# RelayBoard1.net
KiCad netlist of a schematic drawn in EAGLE
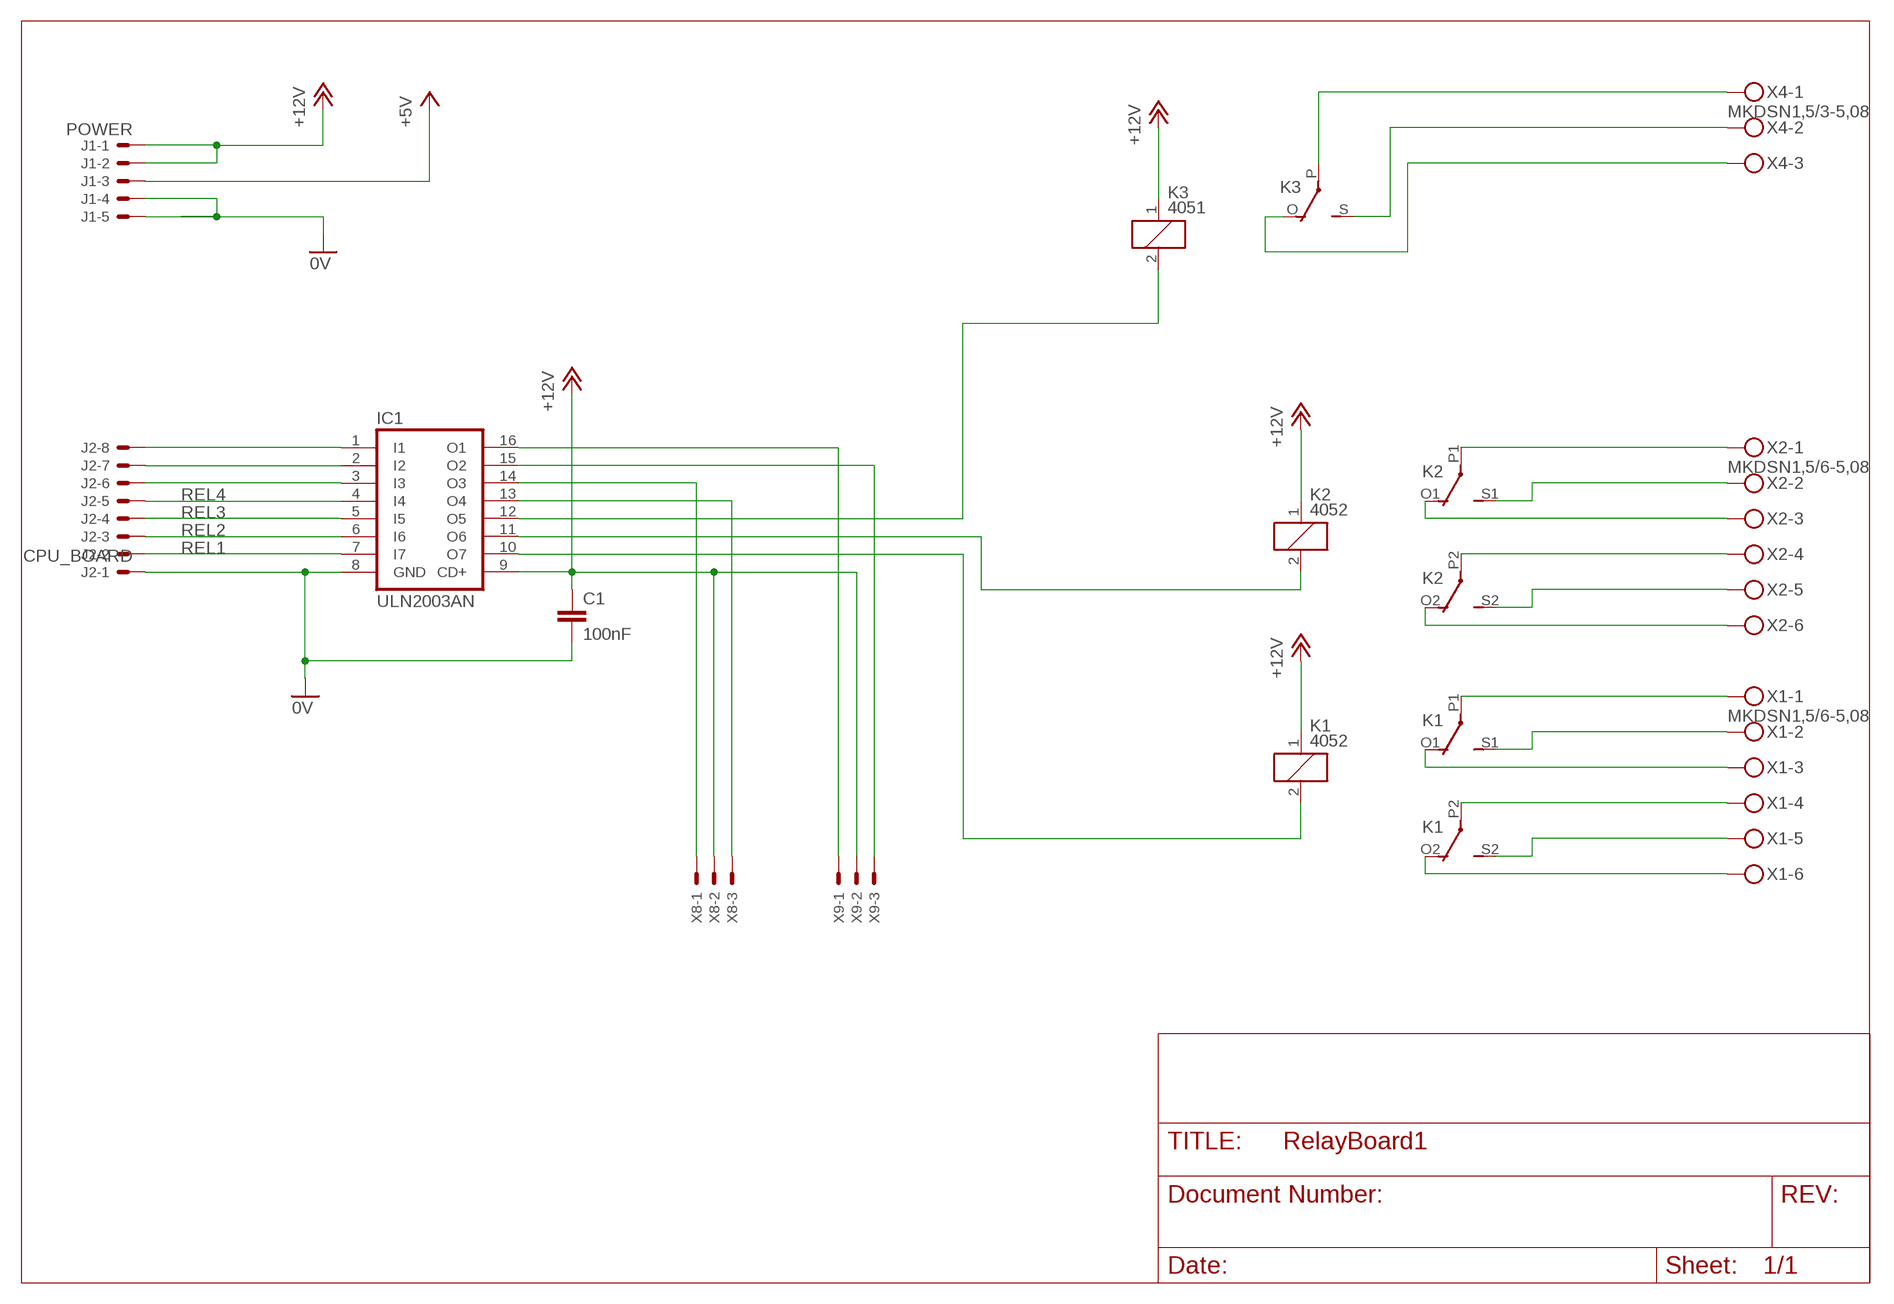
[diagram p0: schematic, sheet 1]

(export (version "E")
  (design (tool "Eeschema 10.0.6"))
  (components
    (comp (ref "C1")
      (value "100nF")
      (footprint "eagle-import:C025-025X050")
      (libsource (lib "eagle-import") (part "C-EU025-025X050"))
    )
    (comp (ref "IC1")
      (value "ULN2003AN")
      (footprint "eagle-import:DIL16")
      (libsource (lib "eagle-import") (part "ULN2003AN"))
    )
    (comp (ref "J1")
      (value "POWER")
      (footprint "eagle-import:6410-05")
      (libsource (lib "eagle-import") (part "22-?-0527-2051"))
    )
    (comp (ref "J2")
      (value "CPU_BOARD")
      (footprint "eagle-import:6410-08")
      (libsource (lib "eagle-import") (part "22-?-0827-2081"))
    )
    (comp (ref "K1")
      (value "4052")
      (footprint "eagle-import:F4052")
      (libsource (lib "eagle-import") (part "4052"))
    )
    (comp (ref "K2")
      (value "4052")
      (footprint "eagle-import:F4052")
      (libsource (lib "eagle-import") (part "4052"))
    )
    (comp (ref "K3")
      (value "4051")
      (footprint "eagle-import:G2R")
      (fields (field (name "OC_FARNELL") "1569185"))
      (libsource (lib "eagle-import") (part "G2R"))
    )
    (comp (ref "X1")
      (value "MKDSN1,5/6-5,08")
      (footprint "eagle-import:MKDSN1,5_6-5,08")
      (fields (field (name "MPN") "SMKDSN1,5/6-5,08"))
      (libsource (lib "eagle-import") (part "MKDSN1,5/6-5,08"))
    )
    (comp (ref "X2")
      (value "MKDSN1,5/6-5,08")
      (footprint "eagle-import:MKDSN1,5_6-5,08")
      (fields (field (name "MPN") "SMKDSN1,5/6-5,08"))
      (libsource (lib "eagle-import") (part "MKDSN1,5/6-5,08"))
    )
    (comp (ref "X4")
      (value "MKDSN1,5/3-5,08")
      (footprint "eagle-import:MKDSN1,5_3-5,08")
      (fields
        (field (name "MPN") "SMKDSN1,5/3-5,08")
        (field (name "MPN_1") "SMKDSN1,5/3-5,08")
        (field (name "OC_FARNELL") "1792904")
        (field (name "OC_NEWARK") "70R0299")
      )
      (libsource (lib "eagle-import") (part "MKDSN1,5/3-5,08"))
    )
    (comp (ref "X8")
      (value "KK-156-3")
      (footprint "eagle-import:KK-156-3")
      (libsource (lib "eagle-import") (part "KK-156-3"))
    )
    (comp (ref "X9")
      (value "KK-156-3")
      (footprint "eagle-import:KK-156-3")
      (libsource (lib "eagle-import") (part "KK-156-3"))
    )
  )
  (nets
    (net (code "1") (name "+5V") (class "Default")
      (node (ref "J1") (pin "3") (pinfunction "S_3") (pintype "passive"))
    )
    (net (code "2") (name "+12V") (class "Default")
      (node (ref "C1") (pin "1") (pinfunction "1_1") (pintype "passive"))
      (node (ref "IC1") (pin "9") (pinfunction "CD+_9") (pintype "passive"))
      (node (ref "J1") (pin "1") (pinfunction "S_1") (pintype "passive"))
      (node (ref "J1") (pin "2") (pinfunction "S_2") (pintype "passive"))
      (node (ref "K1") (pin "1") (pinfunction "1_1") (pintype "passive"))
      (node (ref "K2") (pin "1") (pinfunction "1_1") (pintype "passive"))
      (node (ref "K3") (pin "1") (pinfunction "1_1") (pintype "passive"))
      (node (ref "X8") (pin "2") (pinfunction "S_2") (pintype "passive"))
      (node (ref "X9") (pin "2") (pinfunction "S_2") (pintype "passive"))
    )
    (net (code "3") (name "/REL1") (class "Default")
      (node (ref "IC1") (pin "7") (pinfunction "I7_7") (pintype "input"))
      (node (ref "J2") (pin "2") (pinfunction "S_2") (pintype "passive"))
    )
    (net (code "4") (name "/REL2") (class "Default")
      (node (ref "IC1") (pin "6") (pinfunction "I6_6") (pintype "input"))
      (node (ref "J2") (pin "3") (pinfunction "S_3") (pintype "passive"))
    )
    (net (code "5") (name "/REL3") (class "Default")
      (node (ref "IC1") (pin "5") (pinfunction "I5_5") (pintype "input"))
      (node (ref "J2") (pin "4") (pinfunction "S_4") (pintype "passive"))
    )
    (net (code "6") (name "/REL4") (class "Default")
      (node (ref "IC1") (pin "4") (pinfunction "I4_4") (pintype "input"))
      (node (ref "J2") (pin "5") (pinfunction "S_5") (pintype "passive"))
    )
    (net (code "7") (name "0V") (class "Default")
      (node (ref "C1") (pin "2") (pinfunction "2_2") (pintype "passive"))
      (node (ref "IC1") (pin "8") (pinfunction "GND_8") (pintype "power_in"))
      (node (ref "J1") (pin "4") (pinfunction "S_4") (pintype "passive"))
      (node (ref "J1") (pin "5") (pinfunction "S_5") (pintype "passive"))
      (node (ref "J2") (pin "1") (pinfunction "S_1") (pintype "passive"))
    )
    (net (code "8") (name "Net-(IC1-I1)") (class "Default")
      (node (ref "IC1") (pin "1") (pinfunction "I1_1") (pintype "input"))
      (node (ref "J2") (pin "8") (pinfunction "S_8") (pintype "passive"))
    )
    (net (code "9") (name "Net-(IC1-I2)") (class "Default")
      (node (ref "IC1") (pin "2") (pinfunction "I2_2") (pintype "input"))
      (node (ref "J2") (pin "7") (pinfunction "S_7") (pintype "passive"))
    )
    (net (code "10") (name "Net-(IC1-I3)") (class "Default")
      (node (ref "IC1") (pin "3") (pinfunction "I3_3") (pintype "input"))
      (node (ref "J2") (pin "6") (pinfunction "S_6") (pintype "passive"))
    )
    (net (code "11") (name "Net-(IC1-O1)") (class "Default")
      (node (ref "IC1") (pin "16") (pinfunction "O1_16") (pintype "open_collector"))
      (node (ref "X9") (pin "1") (pinfunction "S_1") (pintype "passive"))
    )
    (net (code "12") (name "Net-(IC1-O2)") (class "Default")
      (node (ref "IC1") (pin "15") (pinfunction "O2_15") (pintype "open_collector"))
      (node (ref "X9") (pin "3") (pinfunction "S_3") (pintype "passive"))
    )
    (net (code "13") (name "Net-(IC1-O3)") (class "Default")
      (node (ref "IC1") (pin "14") (pinfunction "O3_14") (pintype "open_collector"))
      (node (ref "X8") (pin "1") (pinfunction "S_1") (pintype "passive"))
    )
    (net (code "14") (name "Net-(IC1-O4)") (class "Default")
      (node (ref "IC1") (pin "13") (pinfunction "O4_13") (pintype "open_collector"))
      (node (ref "X8") (pin "3") (pinfunction "S_3") (pintype "passive"))
    )
    (net (code "15") (name "Net-(IC1-O5)") (class "Default")
      (node (ref "IC1") (pin "12") (pinfunction "O5_12") (pintype "open_collector"))
      (node (ref "K3") (pin "2") (pinfunction "2_2") (pintype "passive"))
    )
    (net (code "16") (name "Net-(IC1-O6)") (class "Default")
      (node (ref "IC1") (pin "11") (pinfunction "O6_11") (pintype "open_collector"))
      (node (ref "K2") (pin "2") (pinfunction "2_2") (pintype "passive"))
    )
    (net (code "17") (name "Net-(IC1-O7)") (class "Default")
      (node (ref "IC1") (pin "10") (pinfunction "O7_10") (pintype "open_collector"))
      (node (ref "K1") (pin "2") (pinfunction "2_2") (pintype "passive"))
    )
    (net (code "18") (name "Net-(K1B-O)") (class "Default")
      (node (ref "K1") (pin "O1") (pinfunction "O_O1") (pintype "passive"))
      (node (ref "X1") (pin "3") (pinfunction "KL_3") (pintype "passive"))
    )
    (net (code "19") (name "Net-(K1B-P)") (class "Default")
      (node (ref "K1") (pin "P1") (pinfunction "P_P1") (pintype "passive"))
      (node (ref "X1") (pin "1") (pinfunction "KL_1") (pintype "passive"))
    )
    (net (code "20") (name "Net-(K1B-S)") (class "Default")
      (node (ref "K1") (pin "S1") (pinfunction "S_S1") (pintype "passive"))
      (node (ref "X1") (pin "2") (pinfunction "KL_2") (pintype "passive"))
    )
    (net (code "21") (name "Net-(K1C-O)") (class "Default")
      (node (ref "K1") (pin "O2") (pinfunction "O_O2") (pintype "passive"))
      (node (ref "X1") (pin "6") (pinfunction "KL_6") (pintype "passive"))
    )
    (net (code "22") (name "Net-(K1C-P)") (class "Default")
      (node (ref "K1") (pin "P2") (pinfunction "P_P2") (pintype "passive"))
      (node (ref "X1") (pin "4") (pinfunction "KL_4") (pintype "passive"))
    )
    (net (code "23") (name "Net-(K1C-S)") (class "Default")
      (node (ref "K1") (pin "S2") (pinfunction "S_S2") (pintype "passive"))
      (node (ref "X1") (pin "5") (pinfunction "KL_5") (pintype "passive"))
    )
    (net (code "24") (name "Net-(K2B-O)") (class "Default")
      (node (ref "K2") (pin "O1") (pinfunction "O_O1") (pintype "passive"))
      (node (ref "X2") (pin "3") (pinfunction "KL_3") (pintype "passive"))
    )
    (net (code "25") (name "Net-(K2B-P)") (class "Default")
      (node (ref "K2") (pin "P1") (pinfunction "P_P1") (pintype "passive"))
      (node (ref "X2") (pin "1") (pinfunction "KL_1") (pintype "passive"))
    )
    (net (code "26") (name "Net-(K2B-S)") (class "Default")
      (node (ref "K2") (pin "S1") (pinfunction "S_S1") (pintype "passive"))
      (node (ref "X2") (pin "2") (pinfunction "KL_2") (pintype "passive"))
    )
    (net (code "27") (name "Net-(K2C-O)") (class "Default")
      (node (ref "K2") (pin "O2") (pinfunction "O_O2") (pintype "passive"))
      (node (ref "X2") (pin "6") (pinfunction "KL_6") (pintype "passive"))
    )
    (net (code "28") (name "Net-(K2C-P)") (class "Default")
      (node (ref "K2") (pin "P2") (pinfunction "P_P2") (pintype "passive"))
      (node (ref "X2") (pin "4") (pinfunction "KL_4") (pintype "passive"))
    )
    (net (code "29") (name "Net-(K2C-S)") (class "Default")
      (node (ref "K2") (pin "S2") (pinfunction "S_S2") (pintype "passive"))
      (node (ref "X2") (pin "5") (pinfunction "KL_5") (pintype "passive"))
    )
    (net (code "30") (name "Net-(X4A-KL)") (class "Default")
      (node (ref "K3") (pin "P") (pinfunction "P_P") (pintype "passive"))
      (node (ref "X4") (pin "1") (pinfunction "KL_1") (pintype "passive"))
    )
    (net (code "31") (name "Net-(X4B-KL)") (class "Default")
      (node (ref "K3") (pin "S") (pinfunction "S_S") (pintype "passive"))
      (node (ref "X4") (pin "2") (pinfunction "KL_2") (pintype "passive"))
    )
    (net (code "32") (name "Net-(X4C-KL)") (class "Default")
      (node (ref "K3") (pin "O") (pinfunction "O_O") (pintype "passive"))
      (node (ref "X4") (pin "3") (pinfunction "KL_3") (pintype "passive"))
    )
  )
)
